# practice.net
KiCad netlist of a schematic drawn in EAGLE
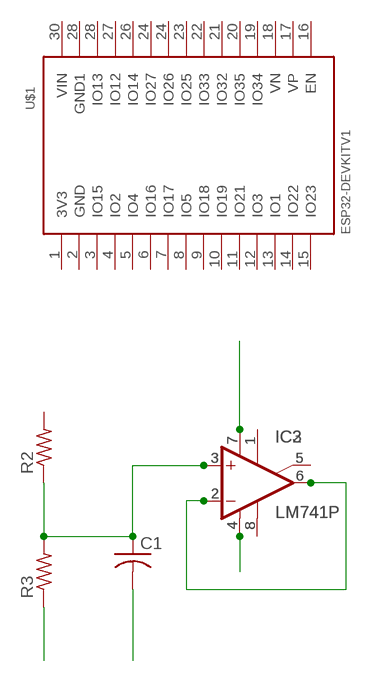
[diagram p0: schematic, sheet 1]

(export (version "E")
  (design (tool "Eeschema 10.0.6"))
  (components
    (comp (ref "C1")
      (value "C-US025-040X050")
      (footprint "eagle-import:C025-040X050")
      (libsource (lib "eagle-import") (part "C-US025-040X050"))
    )
    (comp (ref "IC2")
      (value "LM741P")
      (footprint "eagle-import:DIL08")
      (libsource (lib "eagle-import") (part "741PLM"))
    )
    (comp (ref "IC3")
      (value "LM741P")
      (footprint "eagle-import:DIL08")
      (libsource (lib "eagle-import") (part "741PLM"))
    )
    (comp (ref "R2")
      (value "R-US_0207/10")
      (footprint "eagle-import:0207_10")
      (libsource (lib "eagle-import") (part "R-US_0207/10"))
    )
    (comp (ref "R3")
      (value "R-US_0207/10")
      (footprint "eagle-import:0207_10")
      (libsource (lib "eagle-import") (part "R-US_0207/10"))
    )
    (comp (ref "U$1")
      (value "ESP32DEVKITV1")
      (footprint "eagle-import:ESP32-DEVKITV1")
      (libsource (lib "eagle-import") (part "ESP32DEVKITV1"))
    )
  )
  (nets
    (net (code "1") (name "Net-(IC2-+IN)") (class "Default")
      (node (ref "C1") (pin "1") (pinfunction "1_1") (pintype "passive"))
      (node (ref "IC2") (pin "3") (pinfunction "+IN_3") (pintype "input"))
      (node (ref "IC3") (pin "3") (pinfunction "+IN_3") (pintype "input"))
      (node (ref "R2") (pin "1") (pinfunction "1_1") (pintype "passive"))
      (node (ref "R3") (pin "2") (pinfunction "2_2") (pintype "passive"))
    )
    (net (code "2") (name "Net-(IC2--IN)") (class "Default")
      (node (ref "IC2") (pin "2") (pinfunction "-IN_2") (pintype "input"))
      (node (ref "IC2") (pin "6") (pinfunction "OUT_6") (pintype "output"))
      (node (ref "IC3") (pin "2") (pinfunction "-IN_2") (pintype "input"))
      (node (ref "IC3") (pin "6") (pinfunction "OUT_6") (pintype "output"))
    )
    (net (code "3") (name "Net-(IC2-ON1)") (class "Default")
      (node (ref "IC2") (pin "1") (pinfunction "ON1_1") (pintype "passive"))
      (node (ref "IC3") (pin "1") (pinfunction "ON1_1") (pintype "passive"))
    )
    (net (code "4") (name "Net-(IC2-ON2)") (class "Default")
      (node (ref "IC2") (pin "5") (pinfunction "ON2_5") (pintype "passive"))
      (node (ref "IC3") (pin "5") (pinfunction "ON2_5") (pintype "passive"))
    )
    (net (code "5") (name "Net-(IC2-OPT)") (class "Default")
      (node (ref "IC2") (pin "8") (pinfunction "OPT_8") (pintype "passive"))
      (node (ref "IC3") (pin "8") (pinfunction "OPT_8") (pintype "passive"))
    )
    (net (code "6") (name "Net-(IC2-V+)") (class "Default")
      (node (ref "IC2") (pin "7") (pinfunction "V+_7") (pintype "power_in"))
      (node (ref "IC3") (pin "7") (pinfunction "V+_7") (pintype "power_in"))
    )
    (net (code "7") (name "Net-(IC2-V-)") (class "Default")
      (node (ref "IC2") (pin "4") (pinfunction "V-_4") (pintype "power_in"))
      (node (ref "IC3") (pin "4") (pinfunction "V-_4") (pintype "power_in"))
    )
    (net (code "8") (name "unconnected-(C1-Pad2)") (class "Default")
      (node (ref "C1") (pin "2") (pinfunction "2_2") (pintype "passive"))
    )
    (net (code "9") (name "unconnected-(R2-Pad2)") (class "Default")
      (node (ref "R2") (pin "2") (pinfunction "2_2") (pintype "passive"))
    )
    (net (code "10") (name "unconnected-(R3-Pad1)") (class "Default")
      (node (ref "R3") (pin "1") (pinfunction "1_1") (pintype "passive"))
    )
    (net (code "11") (name "unconnected-(U$1-3V3-Pad1)") (class "Default")
      (node (ref "U$1") (pin "1") (pinfunction "3V3_1") (pintype "bidirectional"))
    )
    (net (code "12") (name "unconnected-(U$1-EN-Pad16)") (class "Default")
      (node (ref "U$1") (pin "16") (pinfunction "EN_16") (pintype "bidirectional"))
    )
    (net (code "13") (name "unconnected-(U$1-GND-Pad2)") (class "Default")
      (node (ref "U$1") (pin "2") (pinfunction "GND_2") (pintype "bidirectional"))
    )
    (net (code "14") (name "unconnected-(U$1-GND1-Pad28)") (class "Default")
      (node (ref "U$1") (pin "28") (pinfunction "GND1_28") (pintype "bidirectional"))
    )
    (net (code "15") (name "unconnected-(U$1-IO1-Pad13)") (class "Default")
      (node (ref "U$1") (pin "13") (pinfunction "IO1_13") (pintype "bidirectional"))
    )
    (net (code "16") (name "unconnected-(U$1-IO2-Pad4)") (class "Default")
      (node (ref "U$1") (pin "4") (pinfunction "IO2_4") (pintype "bidirectional"))
    )
    (net (code "17") (name "unconnected-(U$1-IO3-Pad12)") (class "Default")
      (node (ref "U$1") (pin "12") (pinfunction "IO3_12") (pintype "bidirectional"))
    )
    (net (code "18") (name "unconnected-(U$1-IO4-Pad5)") (class "Default")
      (node (ref "U$1") (pin "5") (pinfunction "IO4_5") (pintype "bidirectional"))
    )
    (net (code "19") (name "unconnected-(U$1-IO5-Pad8)") (class "Default")
      (node (ref "U$1") (pin "8") (pinfunction "IO5_8") (pintype "bidirectional"))
    )
    (net (code "20") (name "unconnected-(U$1-IO12-Pad27)") (class "Default")
      (node (ref "U$1") (pin "27") (pinfunction "IO12_27") (pintype "bidirectional"))
    )
    (net (code "21") (name "unconnected-(U$1-IO13-Pad28)") (class "Default")
      (node (ref "U$1") (pin "28") (pinfunction "IO13_28") (pintype "bidirectional"))
    )
    (net (code "22") (name "unconnected-(U$1-IO14-Pad26)") (class "Default")
      (node (ref "U$1") (pin "26") (pinfunction "IO14_26") (pintype "bidirectional"))
    )
    (net (code "23") (name "unconnected-(U$1-IO15-Pad3)") (class "Default")
      (node (ref "U$1") (pin "3") (pinfunction "IO15_3") (pintype "bidirectional"))
    )
    (net (code "24") (name "unconnected-(U$1-IO16-Pad6)") (class "Default")
      (node (ref "U$1") (pin "6") (pinfunction "IO16_6") (pintype "bidirectional"))
    )
    (net (code "25") (name "unconnected-(U$1-IO17-Pad7)") (class "Default")
      (node (ref "U$1") (pin "7") (pinfunction "IO17_7") (pintype "bidirectional"))
    )
    (net (code "26") (name "unconnected-(U$1-IO18-Pad9)") (class "Default")
      (node (ref "U$1") (pin "9") (pinfunction "IO18_9") (pintype "bidirectional"))
    )
    (net (code "27") (name "unconnected-(U$1-IO19-Pad10)") (class "Default")
      (node (ref "U$1") (pin "10") (pinfunction "IO19_10") (pintype "bidirectional"))
    )
    (net (code "28") (name "unconnected-(U$1-IO21-Pad11)") (class "Default")
      (node (ref "U$1") (pin "11") (pinfunction "IO21_11") (pintype "bidirectional"))
    )
    (net (code "29") (name "unconnected-(U$1-IO22-Pad14)") (class "Default")
      (node (ref "U$1") (pin "14") (pinfunction "IO22_14") (pintype "bidirectional"))
    )
    (net (code "30") (name "unconnected-(U$1-IO23-Pad15)") (class "Default")
      (node (ref "U$1") (pin "15") (pinfunction "IO23_15") (pintype "bidirectional"))
    )
    (net (code "31") (name "unconnected-(U$1-IO25-Pad23)") (class "Default")
      (node (ref "U$1") (pin "23") (pinfunction "IO25_23") (pintype "bidirectional"))
    )
    (net (code "32") (name "unconnected-(U$1-IO26-Pad24)") (class "Default")
      (node (ref "U$1") (pin "24") (pinfunction "IO26_24") (pintype "bidirectional"))
    )
    (net (code "33") (name "unconnected-(U$1-IO27-Pad24)") (class "Default")
      (node (ref "U$1") (pin "24") (pinfunction "IO27_24") (pintype "bidirectional"))
    )
    (net (code "34") (name "unconnected-(U$1-IO32-Pad21)") (class "Default")
      (node (ref "U$1") (pin "21") (pinfunction "IO32_21") (pintype "bidirectional"))
    )
    (net (code "35") (name "unconnected-(U$1-IO33-Pad22)") (class "Default")
      (node (ref "U$1") (pin "22") (pinfunction "IO33_22") (pintype "bidirectional"))
    )
    (net (code "36") (name "unconnected-(U$1-IO34-Pad19)") (class "Default")
      (node (ref "U$1") (pin "19") (pinfunction "IO34_19") (pintype "bidirectional"))
    )
    (net (code "37") (name "unconnected-(U$1-IO35-Pad20)") (class "Default")
      (node (ref "U$1") (pin "20") (pinfunction "IO35_20") (pintype "bidirectional"))
    )
    (net (code "38") (name "unconnected-(U$1-VIN-Pad30)") (class "Default")
      (node (ref "U$1") (pin "30") (pinfunction "VIN_30") (pintype "bidirectional"))
    )
    (net (code "39") (name "unconnected-(U$1-VN-Pad18)") (class "Default")
      (node (ref "U$1") (pin "18") (pinfunction "VN_18") (pintype "bidirectional"))
    )
    (net (code "40") (name "unconnected-(U$1-VP-Pad17)") (class "Default")
      (node (ref "U$1") (pin "17") (pinfunction "VP_17") (pintype "bidirectional"))
    )
  )
)
